# FOTA_Burn_Buffer.net
KiCad netlist of a schematic drawn in Altium Designer
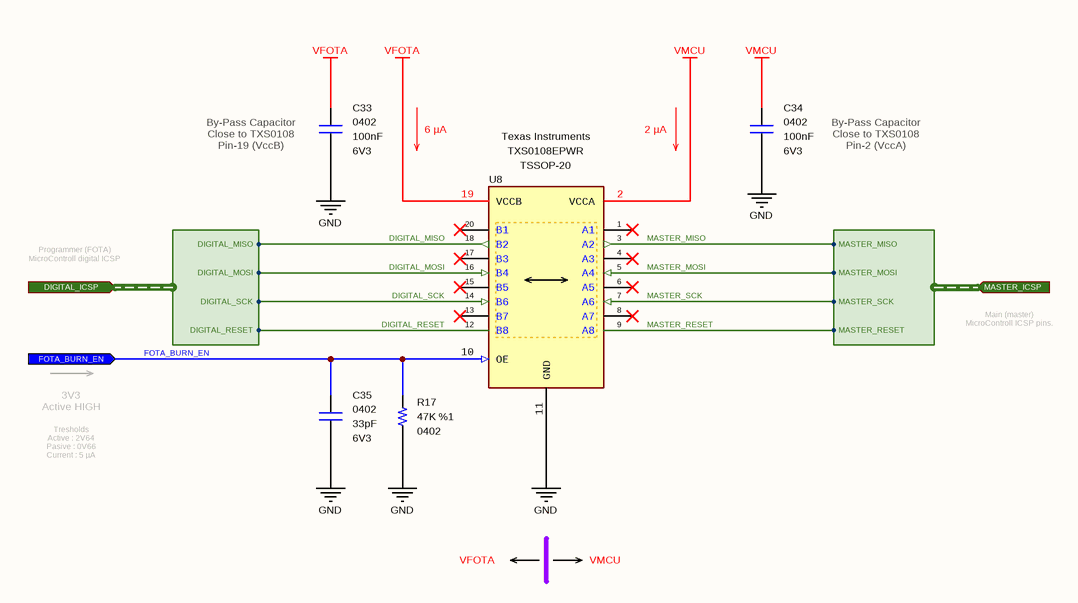
[diagram p0: FOTA Burn Buffer.SchDoc]

(export (version "E")
  (design (tool "Eeschema 10.0.6"))
  (components
    (comp (ref "C33")
      (value "100nF")
      (footprint "CAPACITOR_0402")
      (description "Capacitor - 100nF [0402-6V3] (Ceramic)")
      (fields
        (field (name "TOLERANCE") "%10")
        (field (name "CASE") "0402")
        (field (name "VOLTAGE") "6V3")
        (field (name "MANUFACTURER PART NUMBER") "04026D104KAT4A")
      )
      (libsource (lib "Ovoo_Library") (part "Capacitor - 100nF [0402-6V3]"))
    )
    (comp (ref "C34")
      (value "100nF")
      (footprint "CAPACITOR_0402")
      (description "Capacitor - 100nF [0402-6V3] (Ceramic)")
      (fields
        (field (name "TOLERANCE") "%10")
        (field (name "CASE") "0402")
        (field (name "VOLTAGE") "6V3")
        (field (name "MANUFACTURER PART NUMBER") "04026D104KAT4A")
      )
      (libsource (lib "Ovoo_Library") (part "Capacitor - 100nF [0402-6V3]"))
    )
    (comp (ref "C35")
      (value "33pF")
      (footprint "CAPACITOR_0402")
      (description "Capacitor - 33pF [0402] (Ceramic)")
      (fields
        (field (name "CASE") "0402")
        (field (name "TOLERANCE") "10%")
        (field (name "VOLTAGE") "6V3")
        (field (name "MANUFACTURER PART NUMBER") "C0402C330J9RACAUTO")
      )
      (libsource (lib "Ovoo_Library") (part "Capacitor - 33pF [0402-6V3]"))
    )
    (comp (ref "R17")
      (value "47K")
      (footprint "RESISTOR_0402")
      (description "Thick Film Resistors - SMD 1/16 W 47 Kohms 1%")
      (fields
        (field (name "TOLERANCE") "%1")
        (field (name "CASE") "0402")
        (field (name "MANUFACTURER PART NUMBER") "CRCW040247K0FKED")
        (field (name "Comment") "47K - 0402 - %1 - 1/16W")
      )
      (libsource (lib "Ovoo_Library") (part "Resistor - 47K"))
    )
    (comp (ref "U8")
      (value "Voltage Level Shifter")
      (footprint "TSSOP-20")
      (description "Translation - Voltage Levels 8B Bidir Vltg-Level Translator")
      (fields
        (field (name "MOUSER PART NUMBER") "595-TXS0108EPWR")
        (field (name "MANUFACTURER PART NUMBER") "TXS0108EPWR")
        (field (name "CASE") "TSSOP-20")
        (field (name "MANUFACTURER NAME") "Texas Instruments")
      )
      (libsource (lib "Ovoo_Library") (part "IC - TXS0108EPW"))
    )
  )
  (nets
    (net (code "3") (name "/DIGITAL_MISO") (class "Default")
      (node (ref "U8") (pin "18") (pinfunction "B2_18") (pintype "output"))
    )
    (net (code "4") (name "/DIGITAL_MOSI") (class "Default")
      (node (ref "U8") (pin "16") (pinfunction "B4_16") (pintype "input"))
    )
    (net (code "5") (name "/DIGITAL_RESET") (class "Default")
      (node (ref "U8") (pin "12") (pinfunction "B8_12") (pintype "passive"))
    )
    (net (code "6") (name "/DIGITAL_SCK") (class "Default")
      (node (ref "U8") (pin "14") (pinfunction "B6_14") (pintype "input"))
    )
    (net (code "7") (name "/FOTA_BURN_EN") (class "Default")
      (node (ref "C35") (pin "1") (pinfunction "1_1") (pintype "passive"))
      (node (ref "R17") (pin "2") (pinfunction "2_2") (pintype "passive"))
      (node (ref "U8") (pin "10") (pinfunction "OE_10") (pintype "input"))
    )
    (net (code "8") (name "/MASTER_MISO") (class "Default")
      (node (ref "U8") (pin "3") (pinfunction "A2_3") (pintype "output"))
    )
    (net (code "9") (name "/MASTER_MOSI") (class "Default")
      (node (ref "U8") (pin "5") (pinfunction "A4_5") (pintype "input"))
    )
    (net (code "10") (name "/MASTER_RESET") (class "Default")
      (node (ref "U8") (pin "9") (pinfunction "A8_9") (pintype "passive"))
    )
    (net (code "11") (name "/MASTER_SCK") (class "Default")
      (node (ref "U8") (pin "7") (pinfunction "A6_7") (pintype "input"))
    )
    (net (code "14") (name "GND") (class "Default")
      (node (ref "C33") (pin "1") (pinfunction "1_1") (pintype "passive"))
      (node (ref "C34") (pin "1") (pinfunction "1_1") (pintype "passive"))
      (node (ref "C35") (pin "2") (pinfunction "2_2") (pintype "passive"))
      (node (ref "R17") (pin "1") (pinfunction "1_1") (pintype "passive"))
      (node (ref "U8") (pin "11") (pinfunction "GND_11") (pintype "passive"))
    )
    (net (code "15") (name "VFOTA") (class "Default")
      (node (ref "C33") (pin "2") (pinfunction "2_2") (pintype "passive"))
      (node (ref "U8") (pin "19") (pinfunction "VCCB_19") (pintype "power_in"))
    )
    (net (code "16") (name "VMCU") (class "Default")
      (node (ref "C34") (pin "2") (pinfunction "2_2") (pintype "passive"))
      (node (ref "U8") (pin "2") (pinfunction "VCCA_2") (pintype "power_in"))
    )
    (net (code "17") (name "unconnected-(U8-A1-Pad1)") (class "Default")
      (node (ref "U8") (pin "1") (pinfunction "A1_1") (pintype "passive+no_connect"))
    )
    (net (code "18") (name "unconnected-(U8-A3-Pad4)") (class "Default")
      (node (ref "U8") (pin "4") (pinfunction "A3_4") (pintype "passive+no_connect"))
    )
    (net (code "19") (name "unconnected-(U8-A5-Pad6)") (class "Default")
      (node (ref "U8") (pin "6") (pinfunction "A5_6") (pintype "passive+no_connect"))
    )
    (net (code "20") (name "unconnected-(U8-A7-Pad8)") (class "Default")
      (node (ref "U8") (pin "8") (pinfunction "A7_8") (pintype "passive+no_connect"))
    )
    (net (code "21") (name "unconnected-(U8-B1-Pad20)") (class "Default")
      (node (ref "U8") (pin "20") (pinfunction "B1_20") (pintype "passive+no_connect"))
    )
    (net (code "22") (name "unconnected-(U8-B3-Pad17)") (class "Default")
      (node (ref "U8") (pin "17") (pinfunction "B3_17") (pintype "passive+no_connect"))
    )
    (net (code "23") (name "unconnected-(U8-B5-Pad15)") (class "Default")
      (node (ref "U8") (pin "15") (pinfunction "B5_15") (pintype "passive+no_connect"))
    )
    (net (code "24") (name "unconnected-(U8-B7-Pad13)") (class "Default")
      (node (ref "U8") (pin "13") (pinfunction "B7_13") (pintype "passive+no_connect"))
    )
  )
)
